# 5V0_VoltageReg.net
KiCad netlist of a schematic drawn in Altium Designer
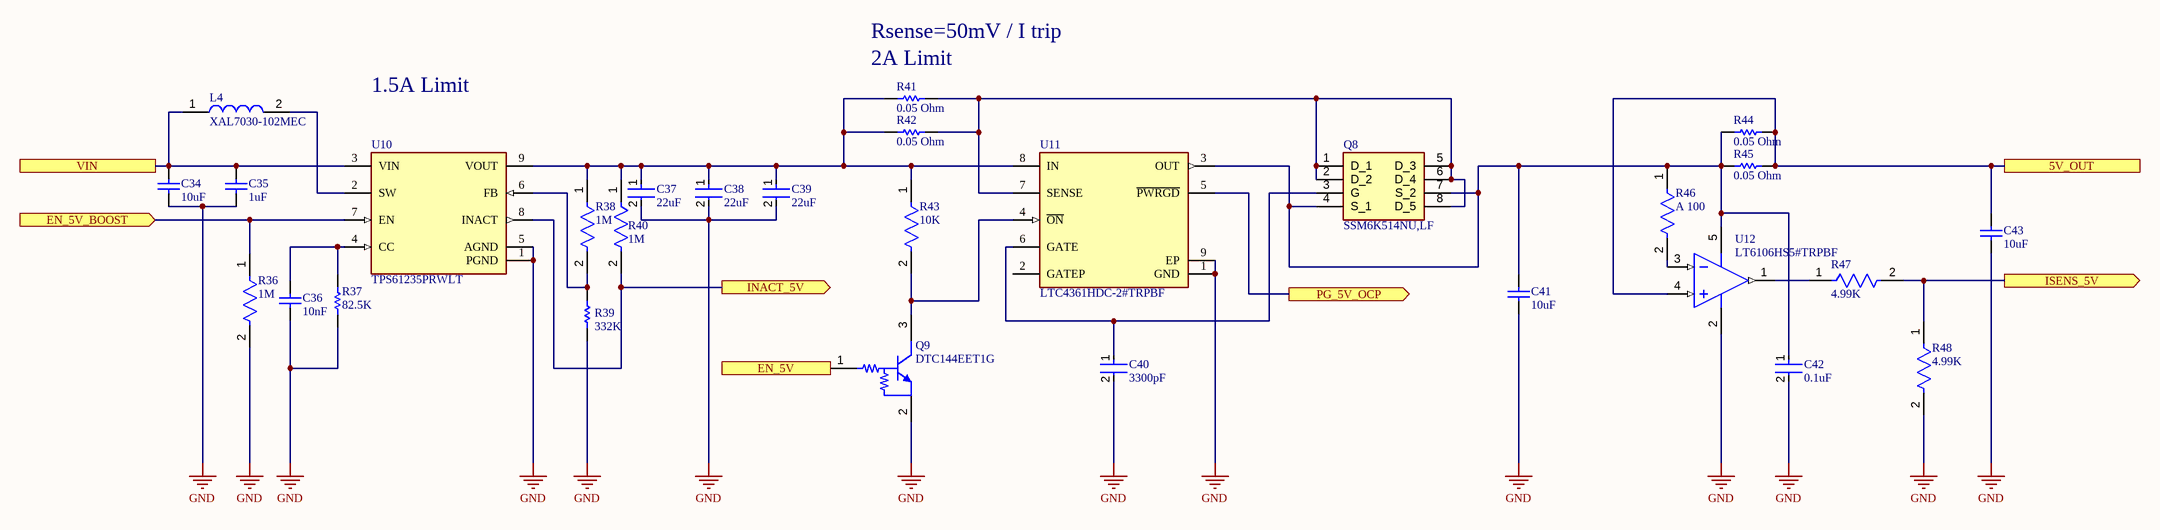
[diagram p0: 5V0_VoltageReg.SchDoc]

(export (version "E")
  (design (tool "Eeschema 10.0.6"))
  (components
    (comp (ref "C34")
      (value "10uF")
      (footprint "CAPC2013X140X45NL15T25")
      (fields (field (name "PART NUMBER") "GRM21BR71A106KE51L") (field (name "MANUFACTURER") "Murata"))
      (libsource (lib "Altium Content Vault") (part "CAP"))
    )
    (comp (ref "C35")
      (value "1uF")
      (footprint "CAPC1608X90X35ML10T15")
      (fields (field (name "PART NUMBER") "GRM188R71C105KA12J") (field (name "MANUFACTURER") "Murata"))
      (libsource (lib "Altium Content Vault") (part "CAP"))
    )
    (comp (ref "C36")
      (value "10nF")
      (footprint "CAPC1608X90X35LL10T15")
      (description "Chip Capacitor, 10000 pF, +/- 10%, 16 V, -55 to 125 degC, 0603 (1608 Metric), RoHS, Tape and Reel")
      (fields (field (name "MANUFACTURER") "Murata"))
      (libsource (lib "Altium Content Vault") (part "CAP-NP-2"))
    )
    (comp (ref "C37")
      (value "22uF")
      (footprint "FP-GRM21B-0_2-e0_2_0_7-IPC_C")
      (description "Chip Multilayer Ceramic Capacitors for General Purpose, 0805, 22uF, X7T, +22%/-33%, 20%, 10V")
      (fields (field (name "VOLTAGE") "10V") (field (name "TOLERANCE") "20%"))
      (libsource (lib "Altium Content Vault") (part "b4654b650e69147ec39a6b967a45e02"))
    )
    (comp (ref "C38")
      (value "22uF")
      (footprint "FP-GRM21B-0_2-e0_2_0_7-IPC_C")
      (description "Chip Multilayer Ceramic Capacitors for General Purpose, 0805, 22uF, X7T, +22%/-33%, 20%, 10V")
      (fields (field (name "VOLTAGE") "10V") (field (name "TOLERANCE") "20%"))
      (libsource (lib "Altium Content Vault") (part "b4654b650e69147ec39a6b967a45e02"))
    )
    (comp (ref "C39")
      (value "22uF")
      (footprint "FP-GRM21B-0_2-e0_2_0_7-IPC_C")
      (description "Chip Multilayer Ceramic Capacitors for General Purpose, 0805, 22uF, X7T, +22%/-33%, 20%, 10V")
      (fields (field (name "VOLTAGE") "10V") (field (name "TOLERANCE") "20%"))
      (libsource (lib "Altium Content Vault") (part "b4654b650e69147ec39a6b967a45e02"))
    )
    (comp (ref "C40")
      (value "3300pF")
      (footprint "FP-C0603C-CF-MFG")
      (description "CAP CER 3300PF 50V 5% X7R 0603")
      (fields
        (field (name "MANUFACTURER PART NUMBER") "C0603C332J5RACTU")
        (field (name "MANUFACTURER") "KEMET")
      )
      (libsource (lib "Altium Content Vault") (part "b4654b650e69147ec39a6b967a45e02"))
    )
    (comp (ref "C41")
      (value "10uF")
      (footprint "CAPC2013X140X45NL15T25")
      (fields (field (name "PART NUMBER") "GRM21BR71A106KE51L") (field (name "MANUFACTURER") "Murata"))
      (libsource (lib "Altium Content Vault") (part "CAP"))
    )
    (comp (ref "C42")
      (value "0.1uF")
      (footprint "FP-C0603C-CF-MFG")
      (description "CAP CER 0.1UF 50V X7R 0603")
      (fields (field (name "TOLERANCE") "0.1") (field (name "MANUFACTURER") "KEMET"))
      (libsource (lib "Altium Content Vault") (part "b4654b650e69147ec39a6b967a45e02"))
    )
    (comp (ref "C43")
      (value "10uF")
      (footprint "CAPC2013X140X45NL15T25")
      (fields (field (name "PART NUMBER") "GRM21BR71A106KE51L") (field (name "MANUFACTURER") "Murata"))
      (libsource (lib "Altium Content Vault") (part "CAP"))
    )
    (comp (ref "L4")
      (value "XAL7030-102MEC")
      (footprint "XAL7030102MEC")
      (description "Fixed Inductors 1uH Shld 20% 21.8A 5mOhms AECQ2")
      (fields (field (name "MOUSER PART NUMBER") "994-XAL7030-102MEC"))
      (libsource (lib "Hitesh Bhoyar") (part "MSS1278T-104MLD"))
    )
    (comp (ref "Q8")
      (value "SSM6K514NU,LF")
      (footprint "SamacSys:UDFN6B")
      (description "MOSFET (N-Channel)")
      (fields (field (name "MOUSER PART NUMBER") "757-SSM6K514NULF"))
      (libsource (lib "*") (part "SSM6K514NU,LF"))
    )
    (comp (ref "Q9")
      (value "DTC144EET1G")
      (footprint "ONSC-SC-75-3-463-01_V")
      (fields (field (name "MANUFACTURER") "On Semiconductor"))
      (libsource (lib "Altium Content Vault") (part "ONSC-BRT-NPN-B1E2C3-3"))
    )
    (comp (ref "R36")
      (value "1M")
      (footprint "FP-ERJ3EK-IPC_C")
      (description "RES SMD 1M OHM 1% 1/10W 0603")
      (fields (field (name "TOLERANCE") "1%"))
      (libsource (lib "Altium Content Vault") (part "1029c3af85768c4190bb7ad29bc67b5"))
    )
    (comp (ref "R37")
      (value "82.5K")
      (footprint "RESC1608X55X30NL20T10")
      (fields (field (name "MANUFACTURER") "KOA Speer") (field (name "PART NUMBER") "RK73H1JTTD8252F"))
      (libsource (lib "Altium Content Vault") (part "RES"))
    )
    (comp (ref "R38")
      (value "1M")
      (footprint "FP-ERJ3EK-IPC_C")
      (description "RES SMD 1M OHM 1% 1/10W 0603")
      (fields (field (name "TOLERANCE") "1%"))
      (libsource (lib "Altium Content Vault") (part "1029c3af85768c4190bb7ad29bc67b5"))
    )
    (comp (ref "R39")
      (value "332K")
      (footprint "RESC1608X55X30ML15T15")
      (fields (field (name "MANUFACTURER") "Panasonic") (field (name "PART NUMBER") "ERJ-3EKF3323V"))
      (libsource (lib "Altium Content Vault") (part "RES"))
    )
    (comp (ref "R40")
      (value "1M")
      (footprint "FP-ERJ3EK-IPC_C")
      (description "RES SMD 1M OHM 1% 1/10W 0603")
      (fields (field (name "TOLERANCE") "1%"))
      (libsource (lib "Altium Content Vault") (part "1029c3af85768c4190bb7ad29bc67b5"))
    )
    (comp (ref "R41")
      (value "0.05 Ohm")
      (footprint "RESC1608X55X30NL15T15")
      (fields (field (name "MANUFACTURER") "Panasonic") (field (name "PART NUMBER") "ERJ-L03KF50MV"))
      (libsource (lib "Altium Content Vault") (part "RES"))
    )
    (comp (ref "R42")
      (value "0.05 Ohm")
      (footprint "RESC1608X55X30NL15T15")
      (fields (field (name "MANUFACTURER") "Panasonic") (field (name "PART NUMBER") "ERJ-L03KF50MV"))
      (libsource (lib "Altium Content Vault") (part "RES"))
    )
    (comp (ref "R43")
      (value "10K")
      (footprint "FP-RK73B1J-MFG")
      (description "RES 10K OHM 5% 1/10W 0603")
      (fields (field (name "TOLERANCE") "5%"))
      (libsource (lib "Altium Content Vault") (part "1029c3af85768c4190bb7ad29bc67b5"))
    )
    (comp (ref "R44")
      (value "0.05 Ohm")
      (footprint "RESC1608X55X30NL15T15")
      (fields (field (name "MANUFACTURER") "Panasonic") (field (name "PART NUMBER") "ERJ-L03KF50MV"))
      (libsource (lib "Altium Content Vault") (part "RES"))
    )
    (comp (ref "R45")
      (value "0.05 Ohm")
      (footprint "RESC1608X55X30NL15T15")
      (fields (field (name "MANUFACTURER") "Panasonic") (field (name "PART NUMBER") "ERJ-L03KF50MV"))
      (libsource (lib "Altium Content Vault") (part "RES"))
    )
    (comp (ref "R46")
      (value "A 100")
      (footprint "FP-ERA3A-IPC_B")
      (description "RES SMD 100 OHM 0.1% 1/10W 0603")
      (fields (field (name "TOLERANCE") "0.1%"))
      (libsource (lib "Altium Content Vault") (part "1029c3af85768c4190bb7ad29bc67b5"))
    )
    (comp (ref "R47")
      (value "4.99K")
      (footprint "FP-ERA3A-IPC_C")
      (description "RES SMD 4.99KOHM 0.1% 1/10W 0603")
      (fields (field (name "TOLERANCE") "0.1%"))
      (libsource (lib "Altium Content Vault") (part "1029c3af85768c4190bb7ad29bc67b5"))
    )
    (comp (ref "R48")
      (value "4.99K")
      (footprint "FP-ERA3A-IPC_C")
      (description "RES SMD 4.99KOHM 0.1% 1/10W 0603")
      (fields (field (name "TOLERANCE") "0.1%"))
      (libsource (lib "Altium Content Vault") (part "1029c3af85768c4190bb7ad29bc67b5"))
    )
    (comp (ref "U10")
      (value "TPS61235PRWLT")
      (footprint "FP-RWL0009A-MFG")
      (description "IC REG BOOST 5.1V 6.5A 9VQFN")
      (libsource (lib "Altium Content Vault") (part "acef349bc1b9670d2dd112159990667"))
    )
    (comp (ref "U11")
      (value "LTC4361HDC-2#TRPBF")
      (footprint "FP-DC8-8-05-08-1719-IPC_C")
      (description "IC OVP/OCP PROTECTION CTLR 8DFN")
      (libsource (lib "Altium Content Vault") (part "fbb45dfe5e09bf71f23ab0fd2a2f1dd"))
    )
    (comp (ref "U12")
      (value "LT6106HS5#TRPBF")
      (footprint "LT-S5-5-TSOT-23_M")
      (fields
        (field (name "MANUFACTURER") "Linear Technology")
        (field (name "LINEAR TECHNOLOGY PART NUMBER") "LT6106")
      )
      (libsource (lib "Altium Content Vault") (part "LT-LT6106-LTC6101HV-5"))
    )
  )
  (nets
    (net (code "1") (name "/5V_OUT") (class "Default")
      (node (ref "C43") (pin "2") (pinfunction "2_2") (pintype "passive"))
      (node (ref "R44") (pin "2") (pinfunction "2_2") (pintype "passive"))
      (node (ref "R45") (pin "2") (pinfunction "2_2") (pintype "passive"))
      (node (ref "U12") (pin "4") (pinfunction "+IN_4") (pintype "input"))
    )
    (net (code "2") (name "/EN_5V") (class "Default")
      (node (ref "Q9") (pin "1") (pinfunction "B_1") (pintype "passive"))
    )
    (net (code "3") (name "/EN_5V_BOOST") (class "Default")
      (node (ref "R36") (pin "1") (pinfunction "1_1") (pintype "passive"))
      (node (ref "U10") (pin "7") (pinfunction "EN_7") (pintype "input"))
    )
    (net (code "4") (name "/INACT_5V") (class "Default")
      (node (ref "R40") (pin "2") (pinfunction "2_2") (pintype "passive"))
      (node (ref "U10") (pin "8") (pinfunction "INACT_8") (pintype "output"))
    )
    (net (code "5") (name "/ISENS_5V") (class "Default")
      (node (ref "R47") (pin "2") (pinfunction "2_2") (pintype "passive"))
      (node (ref "R48") (pin "1") (pinfunction "1_1") (pintype "passive"))
    )
    (net (code "6") (name "/PG_5V_OCP") (class "Default")
      (node (ref "U11") (pin "5") (pinfunction "~{PWRGD}_5") (pintype "open_collector"))
    )
    (net (code "7") (name "/VIN") (class "Default")
      (node (ref "C34") (pin "2") (pinfunction "2_2") (pintype "passive"))
      (node (ref "C35") (pin "2") (pinfunction "2_2") (pintype "passive"))
      (node (ref "L4") (pin "1") (pinfunction "1_1") (pintype "passive"))
      (node (ref "U10") (pin "3") (pinfunction "VIN_3") (pintype "power_in"))
    )
    (net (code "8") (name "GND") (class "Default")
      (node (ref "C34") (pin "1") (pinfunction "1_1") (pintype "passive"))
      (node (ref "C35") (pin "1") (pinfunction "1_1") (pintype "passive"))
      (node (ref "C36") (pin "1") (pinfunction "1_1") (pintype "passive"))
      (node (ref "C37") (pin "2") (pinfunction "2_2") (pintype "passive"))
      (node (ref "C38") (pin "2") (pinfunction "2_2") (pintype "passive"))
      (node (ref "C39") (pin "2") (pinfunction "2_2") (pintype "passive"))
      (node (ref "C40") (pin "2") (pinfunction "2_2") (pintype "passive"))
      (node (ref "C41") (pin "1") (pinfunction "1_1") (pintype "passive"))
      (node (ref "C42") (pin "2") (pinfunction "2_2") (pintype "passive"))
      (node (ref "C43") (pin "1") (pinfunction "1_1") (pintype "passive"))
      (node (ref "Q9") (pin "2") (pinfunction "E_2") (pintype "passive"))
      (node (ref "R36") (pin "2") (pinfunction "2_2") (pintype "passive"))
      (node (ref "R37") (pin "1") (pinfunction "1_1") (pintype "passive"))
      (node (ref "R39") (pin "1") (pinfunction "1_1") (pintype "passive"))
      (node (ref "R48") (pin "2") (pinfunction "2_2") (pintype "passive"))
      (node (ref "U10") (pin "1") (pinfunction "PGND_1") (pintype "power_in"))
      (node (ref "U10") (pin "5") (pinfunction "AGND_5") (pintype "power_in"))
      (node (ref "U11") (pin "1") (pinfunction "GND_1") (pintype "power_in"))
      (node (ref "U11") (pin "9") (pinfunction "EP_9") (pintype "power_in"))
      (node (ref "U12") (pin "2") (pinfunction "V-_2") (pintype "power_in"))
    )
    (net (code "9") (name "Net-(Q8-D_1)") (class "Default")
      (node (ref "Q8") (pin "1") (pinfunction "D_1_1") (pintype "passive"))
      (node (ref "Q8") (pin "2") (pinfunction "D_2_2") (pintype "passive"))
      (node (ref "Q8") (pin "5") (pinfunction "D_3_5") (pintype "passive"))
      (node (ref "Q8") (pin "6") (pinfunction "D_4_6") (pintype "passive"))
      (node (ref "Q8") (pin "8") (pinfunction "D_5_8") (pintype "passive"))
      (node (ref "R41") (pin "2") (pinfunction "2_2") (pintype "passive"))
      (node (ref "R42") (pin "2") (pinfunction "2_2") (pintype "passive"))
      (node (ref "U11") (pin "7") (pinfunction "SENSE_7") (pintype "passive"))
    )
    (net (code "10") (name "Net-(Q8-G)") (class "Default")
      (node (ref "C40") (pin "1") (pinfunction "1_1") (pintype "passive"))
      (node (ref "Q8") (pin "3") (pinfunction "G_3") (pintype "passive"))
      (node (ref "U11") (pin "6") (pinfunction "GATE_6") (pintype "passive"))
    )
    (net (code "11") (name "Net-(Q8-S_1)") (class "Default")
      (node (ref "C41") (pin "2") (pinfunction "2_2") (pintype "passive"))
      (node (ref "C42") (pin "1") (pinfunction "1_1") (pintype "passive"))
      (node (ref "Q8") (pin "4") (pinfunction "S_1_4") (pintype "passive"))
      (node (ref "Q8") (pin "7") (pinfunction "S_2_7") (pintype "passive"))
      (node (ref "R44") (pin "1") (pinfunction "1_1") (pintype "passive"))
      (node (ref "R45") (pin "1") (pinfunction "1_1") (pintype "passive"))
      (node (ref "R46") (pin "1") (pinfunction "1_1") (pintype "passive"))
      (node (ref "U11") (pin "3") (pinfunction "OUT_3") (pintype "output"))
      (node (ref "U12") (pin "5") (pinfunction "V+_5") (pintype "power_in"))
    )
    (net (code "12") (name "Net-(Q9-C)") (class "Default")
      (node (ref "Q9") (pin "3") (pinfunction "C_3") (pintype "passive"))
      (node (ref "R43") (pin "2") (pinfunction "2_2") (pintype "passive"))
      (node (ref "U11") (pin "4") (pinfunction "~{ON}_4") (pintype "input"))
    )
    (net (code "13") (name "Net-(U10-CC)") (class "Default")
      (node (ref "C36") (pin "2") (pinfunction "2_2") (pintype "passive"))
      (node (ref "R37") (pin "2") (pinfunction "2_2") (pintype "passive"))
      (node (ref "U10") (pin "4") (pinfunction "CC_4") (pintype "input"))
    )
    (net (code "14") (name "Net-(U10-FB)") (class "Default")
      (node (ref "R38") (pin "2") (pinfunction "2_2") (pintype "passive"))
      (node (ref "R39") (pin "2") (pinfunction "2_2") (pintype "passive"))
      (node (ref "U10") (pin "6") (pinfunction "FB_6") (pintype "input"))
    )
    (net (code "15") (name "Net-(U10-SW)") (class "Default")
      (node (ref "L4") (pin "2") (pinfunction "2_2") (pintype "passive"))
      (node (ref "U10") (pin "2") (pinfunction "SW_2") (pintype "power_in"))
    )
    (net (code "16") (name "Net-(U10-VOUT)") (class "Default")
      (node (ref "C37") (pin "1") (pinfunction "1_1") (pintype "passive"))
      (node (ref "C38") (pin "1") (pinfunction "1_1") (pintype "passive"))
      (node (ref "C39") (pin "1") (pinfunction "1_1") (pintype "passive"))
      (node (ref "R38") (pin "1") (pinfunction "1_1") (pintype "passive"))
      (node (ref "R40") (pin "1") (pinfunction "1_1") (pintype "passive"))
      (node (ref "R41") (pin "1") (pinfunction "1_1") (pintype "passive"))
      (node (ref "R42") (pin "1") (pinfunction "1_1") (pintype "passive"))
      (node (ref "R43") (pin "1") (pinfunction "1_1") (pintype "passive"))
      (node (ref "U10") (pin "9") (pinfunction "VOUT_9") (pintype "power_in"))
      (node (ref "U11") (pin "8") (pinfunction "IN_8") (pintype "power_in"))
    )
    (net (code "17") (name "Net-(U12--IN)") (class "Default")
      (node (ref "R46") (pin "2") (pinfunction "2_2") (pintype "passive"))
      (node (ref "U12") (pin "3") (pinfunction "-IN_3") (pintype "input"))
    )
    (net (code "18") (name "Net-(U12-OUT)") (class "Default")
      (node (ref "R47") (pin "1") (pinfunction "1_1") (pintype "passive"))
      (node (ref "U12") (pin "1") (pinfunction "OUT_1") (pintype "output"))
    )
    (net (code "19") (name "unconnected-(U11-GATEP-Pad2)") (class "Default")
      (node (ref "U11") (pin "2") (pinfunction "GATEP_2") (pintype "passive"))
    )
  )
)
